# FPGA.net
KiCad netlist of a schematic drawn in Altium Designer
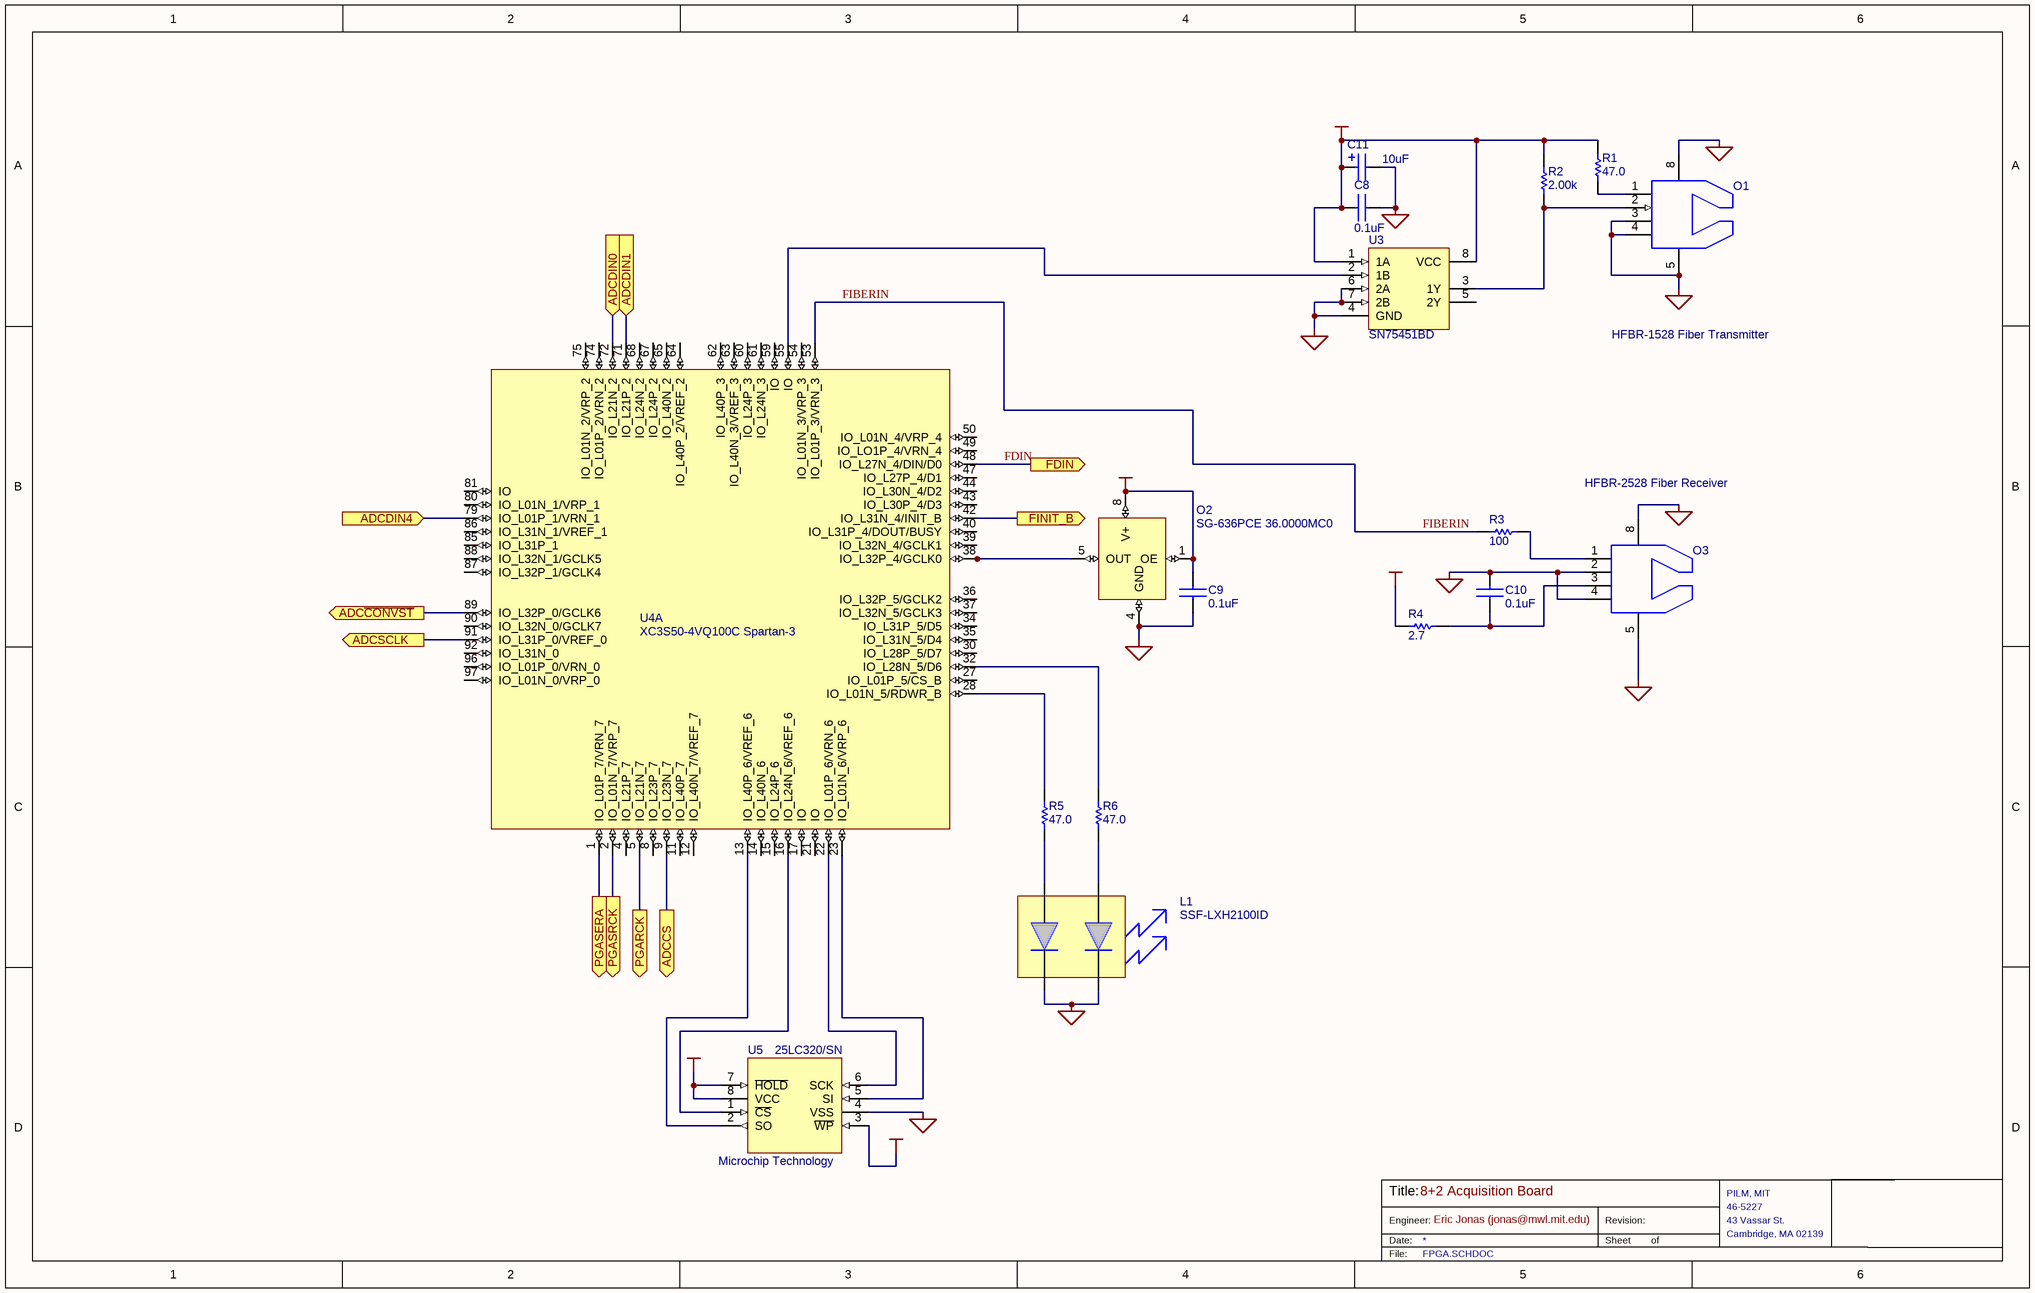
[diagram p0: FPGA.SCHDOC]

(export (version "E")
  (design (tool "Eeschema 10.0.6"))
  (components
    (comp (ref "C8")
      (value "0.1uF")
      (footprint "0603")
      (description "Standard Capacitor")
      (fields (field (name "Comment") "CAPACITOR"))
      (libsource (lib "parts") (part "CAPACITOR"))
    )
    (comp (ref "C9")
      (value "0.1uF")
      (footprint "0603")
      (description "Standard Capacitor")
      (fields (field (name "Comment") "CAPACITOR"))
      (libsource (lib "parts") (part "CAPACITOR"))
    )
    (comp (ref "C10")
      (value "0.1uF")
      (footprint "0603")
      (description "Standard Capacitor")
      (fields (field (name "Comment") "CAPACITOR"))
      (libsource (lib "parts") (part "CAPACITOR"))
    )
    (comp (ref "C11")
      (value "10uF")
      (footprint "3216")
      (description "Standard Capacitor")
      (fields (field (name "Comment") "Tantalum"))
      (libsource (lib "parts") (part "POLCAP"))
    )
    (comp (ref "L1")
      (value "SSF-LXH2100ID")
      (footprint "LUMEX DUAL RT-ANG LED")
      (description "Dual LED")
      (libsource (lib "parts") (part "DUAL LED"))
    )
    (comp (ref "O1")
      (value "HFBR-1528 Fiber Transmitter")
      (footprint "HPVL")
      (description "Low-cost fiber transmitter")
      (libsource (lib "parts") (part "HFBR-1528"))
    )
    (comp (ref "O2")
      (value "SG-636PCE 36.0000MC0")
      (footprint "SG636PCE")
      (description "Epson CMOS/TTL Oscillator")
      (libsource (lib "parts") (part "SG-636PCE"))
    )
    (comp (ref "O3")
      (value "HFBR-2528 Fiber Receiver")
      (footprint "HPVL")
      (description "Low-cost fiber receiver")
      (libsource (lib "parts") (part "HFBR-2528"))
    )
    (comp (ref "R1")
      (value "47.0")
      (footprint "0603")
      (description "Standard Passive Resistor")
      (fields (field (name "Comment") "RESISTOR"))
      (libsource (lib "parts") (part "RESISTOR"))
    )
    (comp (ref "R2")
      (value "2.00k")
      (footprint "0603")
      (description "Standard Passive Resistor")
      (fields (field (name "Comment") "RESISTOR"))
      (libsource (lib "parts") (part "RESISTOR"))
    )
    (comp (ref "R3")
      (value "100")
      (footprint "0603")
      (description "Standard Passive Resistor")
      (fields (field (name "Comment") "RESISTOR"))
      (libsource (lib "parts") (part "RESISTOR"))
    )
    (comp (ref "R4")
      (value "2.7")
      (footprint "0603")
      (description "Standard Passive Resistor")
      (fields (field (name "Comment") "RESISTOR"))
      (libsource (lib "parts") (part "RESISTOR"))
    )
    (comp (ref "R5")
      (value "47.0")
      (footprint "0603")
      (description "Standard Passive Resistor")
      (fields (field (name "Comment") "RESISTOR"))
      (libsource (lib "parts") (part "RESISTOR"))
    )
    (comp (ref "R6")
      (value "47.0")
      (footprint "0603")
      (description "Standard Passive Resistor")
      (fields (field (name "Comment") "RESISTOR"))
      (libsource (lib "parts") (part "RESISTOR"))
    )
    (comp (ref "U3")
      (value "SN75451BD")
      (footprint "SO-G8/E2.5")
      (description "Dual Peripheral Driver")
      (fields (field (name "MANUFACTURER") "Texas Instruments") (field (name "PUBLISHER") "Altium Limited"))
      (libsource (lib "TI Interface Peripheral Driver") (part "SN75451BD"))
    )
    (comp (ref "U4")
      (value "XC3S50-4VQ100C Spartan-3")
      (footprint "F-QFP14X14-G100/N")
      (description "Xilinx Spartan-3 VQ100")
      (libsource (lib "parts") (part "XC3S50-4VQ100C"))
    )
    (comp (ref "U5")
      (value "25LC320/SN")
      (footprint "SO-G8/E2.9")
      (description "32k SPI Bus Serial EEPROM")
      (fields (field (name "VENDOR") "Microchip Technology"))
      (libsource (lib "parts") (part "25LC320-SOIC"))
    )
  )
  (nets
    (net (code "1") (name "+5VCC") (class "Default")
      (node (ref "C11") (pin "1") (pintype "passive"))
      (node (ref "C8") (pin "1") (pintype "passive"))
      (node (ref "R1") (pin "2") (pintype "passive"))
      (node (ref "R2") (pin "2") (pintype "passive"))
      (node (ref "R4") (pin "1") (pintype "passive"))
      (node (ref "U3") (pin "1") (pinfunction "1A_1") (pintype "input"))
      (node (ref "U3") (pin "8") (pinfunction "VCC_8") (pintype "power_in"))
    )
    (net (code "2") (name "/ADCCS") (class "Default")
      (node (ref "U4") (pin "9") (pinfunction "IO_L23N_7_9") (pintype "bidirectional"))
    )
    (net (code "3") (name "/ADCDIN0") (class "Default")
      (node (ref "U4") (pin "72") (pinfunction "IO_L21N_2_72") (pintype "bidirectional"))
    )
    (net (code "4") (name "/ADCDIN1") (class "Default")
      (node (ref "U4") (pin "71") (pinfunction "IO_L21P_2_71") (pintype "bidirectional"))
    )
    (net (code "5") (name "/ADCDIN4") (class "Default")
      (node (ref "U4") (pin "79") (pinfunction "IO_L01P_1/VRN_1_79") (pintype "bidirectional"))
    )
    (net (code "6") (name "/ADCSCLK") (class "Default")
      (node (ref "U4") (pin "91") (pinfunction "IO_L31P_0/VREF_0_91") (pintype "bidirectional"))
    )
    (net (code "7") (name "/ADC~{CONVST}") (class "Default")
      (node (ref "U4") (pin "89") (pinfunction "IO_L32P_0/GCLK6_89") (pintype "bidirectional"))
    )
    (net (code "8") (name "/FDIN") (class "Default")
      (node (ref "U4") (pin "48") (pinfunction "IO_L27N_4/DIN/D0_48") (pintype "bidirectional"))
    )
    (net (code "9") (name "/FIBERIN") (class "Default")
      (node (ref "R3") (pin "1") (pintype "passive"))
      (node (ref "U4") (pin "53") (pinfunction "IO_L01P_3/VRN_3_53") (pintype "bidirectional"))
    )
    (net (code "10") (name "/FINIT_B") (class "Default")
      (node (ref "U4") (pin "42") (pinfunction "IO_L31N_4/INIT_B_42") (pintype "bidirectional"))
    )
    (net (code "11") (name "/PGARCK") (class "Default")
      (node (ref "U4") (pin "5") (pinfunction "IO_L21N_7_5") (pintype "bidirectional"))
    )
    (net (code "12") (name "/PGASERA") (class "Default")
      (node (ref "U4") (pin "1") (pinfunction "IO_L01P_7/VRN_7_1") (pintype "bidirectional"))
    )
    (net (code "13") (name "/PGASRCK") (class "Default")
      (node (ref "U4") (pin "2") (pinfunction "IO_L01N_7/VRP_7_2") (pintype "bidirectional"))
    )
    (net (code "14") (name "GND") (class "Default")
      (node (ref "C10") (pin "2") (pintype "passive"))
      (node (ref "C11") (pin "2") (pintype "passive"))
      (node (ref "C8") (pin "2") (pintype "passive"))
      (node (ref "C9") (pin "2") (pintype "passive"))
      (node (ref "L1") (pin "2") (pinfunction "2_2") (pintype "passive"))
      (node (ref "L1") (pin "4") (pinfunction "C2_4") (pintype "passive"))
      (node (ref "O1") (pin "3") (pintype "power_in"))
      (node (ref "O1") (pin "4") (pintype "power_in"))
      (node (ref "O1") (pin "5") (pintype "power_in"))
      (node (ref "O1") (pin "8") (pintype "power_in"))
      (node (ref "O2") (pin "4") (pinfunction "GND_4") (pintype "bidirectional"))
      (node (ref "O3") (pin "2") (pintype "power_in"))
      (node (ref "O3") (pin "4") (pintype "power_in"))
      (node (ref "O3") (pin "5") (pintype "power_in"))
      (node (ref "O3") (pin "8") (pintype "power_in"))
      (node (ref "U3") (pin "4") (pinfunction "GND_4") (pintype "power_in"))
      (node (ref "U3") (pin "6") (pinfunction "2A_6") (pintype "input"))
      (node (ref "U3") (pin "7") (pinfunction "2B_7") (pintype "input"))
      (node (ref "U5") (pin "4") (pinfunction "VSS_4") (pintype "power_in"))
    )
    (net (code "15") (name "Net-(C10-Pad1)") (class "Default")
      (node (ref "C10") (pin "1") (pintype "passive"))
      (node (ref "O3") (pin "3") (pintype "power_in"))
      (node (ref "R4") (pin "2") (pintype "passive"))
    )
    (net (code "16") (name "Net-(L1-A1)") (class "Default")
      (node (ref "L1") (pin "1") (pinfunction "A1_1") (pintype "passive"))
      (node (ref "R5") (pin "2") (pintype "passive"))
    )
    (net (code "17") (name "Net-(L1-A2)") (class "Default")
      (node (ref "L1") (pin "3") (pinfunction "A2_3") (pintype "passive"))
      (node (ref "R6") (pin "2") (pintype "passive"))
    )
    (net (code "18") (name "Net-(O1-Pad1)") (class "Default")
      (node (ref "O1") (pin "1") (pintype "power_in"))
      (node (ref "R1") (pin "1") (pintype "passive"))
    )
    (net (code "19") (name "Net-(O2-OUT)") (class "Default")
      (node (ref "O2") (pin "5") (pinfunction "OUT_5") (pintype "bidirectional"))
      (node (ref "U4") (pin "38") (pinfunction "IO_L32P_4/GCLK0_38") (pintype "bidirectional"))
    )
    (net (code "20") (name "Net-(O3-Pad1)") (class "Default")
      (node (ref "O3") (pin "1") (pintype "power_in"))
      (node (ref "R3") (pin "2") (pintype "passive"))
    )
    (net (code "21") (name "Net-(U3-1B)") (class "Default")
      (node (ref "U3") (pin "2") (pinfunction "1B_2") (pintype "input"))
      (node (ref "U4") (pin "55") (pinfunction "IO_55") (pintype "bidirectional"))
    )
    (net (code "22") (name "Net-(U3-1Y)") (class "Default")
      (node (ref "O1") (pin "2") (pintype "input"))
      (node (ref "R2") (pin "1") (pintype "passive"))
      (node (ref "U3") (pin "3") (pinfunction "1Y_3") (pintype "open_collector"))
    )
    (net (code "23") (name "Net-(U4A-IO_L01N_5{slash}RDWR_B)") (class "Default")
      (node (ref "R5") (pin "1") (pintype "passive"))
      (node (ref "U4") (pin "28") (pinfunction "IO_L01N_5/RDWR_B_28") (pintype "bidirectional"))
    )
    (net (code "24") (name "Net-(U4A-IO_L01N_6{slash}VRP_6)") (class "Default")
      (node (ref "U4") (pin "23") (pinfunction "IO_L01N_6/VRP_6_23") (pintype "bidirectional"))
      (node (ref "U5") (pin "5") (pinfunction "SI_5") (pintype "input"))
    )
    (net (code "25") (name "Net-(U4A-IO_L01P_6{slash}VRN_6)") (class "Default")
      (node (ref "U4") (pin "22") (pinfunction "IO_L01P_6/VRN_6_22") (pintype "bidirectional"))
      (node (ref "U5") (pin "6") (pinfunction "SCK_6") (pintype "input"))
    )
    (net (code "26") (name "Net-(U4A-IO_L24N_6{slash}VREF_6)") (class "Default")
      (node (ref "U4") (pin "16") (pinfunction "IO_L24N_6/VREF_6_16") (pintype "bidirectional"))
      (node (ref "U5") (pin "1") (pinfunction "~{CS}_1") (pintype "input"))
    )
    (net (code "27") (name "Net-(U4A-IO_L28N_5{slash}D6)") (class "Default")
      (node (ref "R6") (pin "1") (pintype "passive"))
      (node (ref "U4") (pin "32") (pinfunction "IO_L28N_5/D6_32") (pintype "bidirectional"))
    )
    (net (code "28") (name "Net-(U4A-IO_L40P_6{slash}VREF_6)") (class "Default")
      (node (ref "U4") (pin "13") (pinfunction "IO_L40P_6/VREF_6_13") (pintype "bidirectional"))
      (node (ref "U5") (pin "2") (pinfunction "SO_2") (pintype "output"))
    )
    (net (code "29") (name "VCC") (class "Default")
      (node (ref "C9") (pin "1") (pintype "passive"))
      (node (ref "O2") (pin "1") (pinfunction "OE_1") (pintype "bidirectional"))
      (node (ref "O2") (pin "8") (pinfunction "V+_8") (pintype "bidirectional"))
      (node (ref "U5") (pin "3") (pinfunction "~{WP}_3") (pintype "input"))
      (node (ref "U5") (pin "7") (pinfunction "~{HOLD}_7") (pintype "input"))
      (node (ref "U5") (pin "8") (pinfunction "VCC_8") (pintype "power_in"))
    )
    (net (code "30") (name "unconnected-(U3-2Y-Pad5)") (class "Default")
      (node (ref "U3") (pin "5") (pinfunction "2Y_5") (pintype "open_collector"))
    )
    (net (code "31") (name "unconnected-(U4A-IO-Pad17)") (class "Default")
      (node (ref "U4") (pin "17") (pinfunction "IO_17") (pintype "bidirectional"))
    )
    (net (code "32") (name "unconnected-(U4A-IO-Pad21)") (class "Default")
      (node (ref "U4") (pin "21") (pinfunction "IO_21") (pintype "bidirectional"))
    )
    (net (code "33") (name "unconnected-(U4A-IO-Pad59)") (class "Default")
      (node (ref "U4") (pin "59") (pinfunction "IO_59") (pintype "bidirectional"))
    )
    (net (code "34") (name "unconnected-(U4A-IO-Pad81)") (class "Default")
      (node (ref "U4") (pin "81") (pinfunction "IO_81") (pintype "bidirectional"))
    )
    (net (code "35") (name "unconnected-(U4A-IO_L01N_0{slash}VRP_0-Pad97)") (class "Default")
      (node (ref "U4") (pin "97") (pinfunction "IO_L01N_0/VRP_0_97") (pintype "bidirectional"))
    )
    (net (code "36") (name "unconnected-(U4A-IO_L01N_1{slash}VRP_1-Pad80)") (class "Default")
      (node (ref "U4") (pin "80") (pinfunction "IO_L01N_1/VRP_1_80") (pintype "bidirectional"))
    )
    (net (code "37") (name "unconnected-(U4A-IO_L01N_2{slash}VRP_2-Pad75)") (class "Default")
      (node (ref "U4") (pin "75") (pinfunction "IO_L01N_2/VRP_2_75") (pintype "bidirectional"))
    )
    (net (code "38") (name "unconnected-(U4A-IO_L01N_3{slash}VRP_3-Pad54)") (class "Default")
      (node (ref "U4") (pin "54") (pinfunction "IO_L01N_3/VRP_3_54") (pintype "bidirectional"))
    )
    (net (code "39") (name "unconnected-(U4A-IO_L01N_4{slash}VRP_4-Pad50)") (class "Default")
      (node (ref "U4") (pin "50") (pinfunction "IO_L01N_4/VRP_4_50") (pintype "bidirectional"))
    )
    (net (code "40") (name "unconnected-(U4A-IO_L01P_0{slash}VRN_0-Pad96)") (class "Default")
      (node (ref "U4") (pin "96") (pinfunction "IO_L01P_0/VRN_0_96") (pintype "bidirectional"))
    )
    (net (code "41") (name "unconnected-(U4A-IO_L01P_2{slash}VRN_2-Pad74)") (class "Default")
      (node (ref "U4") (pin "74") (pinfunction "IO_L01P_2/VRN_2_74") (pintype "bidirectional"))
    )
    (net (code "42") (name "unconnected-(U4A-IO_L01P_5{slash}CS_B-Pad27)") (class "Default")
      (node (ref "U4") (pin "27") (pinfunction "IO_L01P_5/CS_B_27") (pintype "bidirectional"))
    )
    (net (code "43") (name "unconnected-(U4A-IO_L21P_7-Pad4)") (class "Default")
      (node (ref "U4") (pin "4") (pinfunction "IO_L21P_7_4") (pintype "bidirectional"))
    )
    (net (code "44") (name "unconnected-(U4A-IO_L23P_7-Pad8)") (class "Default")
      (node (ref "U4") (pin "8") (pinfunction "IO_L23P_7_8") (pintype "bidirectional"))
    )
    (net (code "45") (name "unconnected-(U4A-IO_L24N_2-Pad68)") (class "Default")
      (node (ref "U4") (pin "68") (pinfunction "IO_L24N_2_68") (pintype "bidirectional"))
    )
    (net (code "46") (name "unconnected-(U4A-IO_L24N_3-Pad61)") (class "Default")
      (node (ref "U4") (pin "61") (pinfunction "IO_L24N_3_61") (pintype "bidirectional"))
    )
    (net (code "47") (name "unconnected-(U4A-IO_L24P_2-Pad67)") (class "Default")
      (node (ref "U4") (pin "67") (pinfunction "IO_L24P_2_67") (pintype "bidirectional"))
    )
    (net (code "48") (name "unconnected-(U4A-IO_L24P_3-Pad60)") (class "Default")
      (node (ref "U4") (pin "60") (pinfunction "IO_L24P_3_60") (pintype "bidirectional"))
    )
    (net (code "49") (name "unconnected-(U4A-IO_L24P_6-Pad15)") (class "Default")
      (node (ref "U4") (pin "15") (pinfunction "IO_L24P_6_15") (pintype "bidirectional"))
    )
    (net (code "50") (name "unconnected-(U4A-IO_L27P_4{slash}D1-Pad47)") (class "Default")
      (node (ref "U4") (pin "47") (pinfunction "IO_L27P_4/D1_47") (pintype "bidirectional"))
    )
    (net (code "51") (name "unconnected-(U4A-IO_L28P_5{slash}D7-Pad30)") (class "Default")
      (node (ref "U4") (pin "30") (pinfunction "IO_L28P_5/D7_30") (pintype "bidirectional"))
    )
    (net (code "52") (name "unconnected-(U4A-IO_L30N_4{slash}D2-Pad44)") (class "Default")
      (node (ref "U4") (pin "44") (pinfunction "IO_L30N_4/D2_44") (pintype "bidirectional"))
    )
    (net (code "53") (name "unconnected-(U4A-IO_L30P_4{slash}D3-Pad43)") (class "Default")
      (node (ref "U4") (pin "43") (pinfunction "IO_L30P_4/D3_43") (pintype "bidirectional"))
    )
    (net (code "54") (name "unconnected-(U4A-IO_L31N_0-Pad92)") (class "Default")
      (node (ref "U4") (pin "92") (pinfunction "IO_L31N_0_92") (pintype "bidirectional"))
    )
    (net (code "55") (name "unconnected-(U4A-IO_L31N_1{slash}VREF_1-Pad86)") (class "Default")
      (node (ref "U4") (pin "86") (pinfunction "IO_L31N_1/VREF_1_86") (pintype "bidirectional"))
    )
    (net (code "56") (name "unconnected-(U4A-IO_L31N_5{slash}D4-Pad35)") (class "Default")
      (node (ref "U4") (pin "35") (pinfunction "IO_L31N_5/D4_35") (pintype "bidirectional"))
    )
    (net (code "57") (name "unconnected-(U4A-IO_L31P_1-Pad85)") (class "Default")
      (node (ref "U4") (pin "85") (pinfunction "IO_L31P_1_85") (pintype "bidirectional"))
    )
    (net (code "58") (name "unconnected-(U4A-IO_L31P_4{slash}DOUT{slash}BUSY-Pad40)") (class "Default")
      (node (ref "U4") (pin "40") (pinfunction "IO_L31P_4/DOUT/BUSY_40") (pintype "bidirectional"))
    )
    (net (code "59") (name "unconnected-(U4A-IO_L31P_5{slash}D5-Pad34)") (class "Default")
      (node (ref "U4") (pin "34") (pinfunction "IO_L31P_5/D5_34") (pintype "bidirectional"))
    )
    (net (code "60") (name "unconnected-(U4A-IO_L32N_0{slash}GCLK7-Pad90)") (class "Default")
      (node (ref "U4") (pin "90") (pinfunction "IO_L32N_0/GCLK7_90") (pintype "bidirectional"))
    )
    (net (code "61") (name "unconnected-(U4A-IO_L32N_1{slash}GCLK5-Pad88)") (class "Default")
      (node (ref "U4") (pin "88") (pinfunction "IO_L32N_1/GCLK5_88") (pintype "bidirectional"))
    )
    (net (code "62") (name "unconnected-(U4A-IO_L32N_4{slash}GCLK1-Pad39)") (class "Default")
      (node (ref "U4") (pin "39") (pinfunction "IO_L32N_4/GCLK1_39") (pintype "bidirectional"))
    )
    (net (code "63") (name "unconnected-(U4A-IO_L32N_5{slash}GCLK3-Pad37)") (class "Default")
      (node (ref "U4") (pin "37") (pinfunction "IO_L32N_5/GCLK3_37") (pintype "bidirectional"))
    )
    (net (code "64") (name "unconnected-(U4A-IO_L32P_1{slash}GCLK4-Pad87)") (class "Default")
      (node (ref "U4") (pin "87") (pinfunction "IO_L32P_1/GCLK4_87") (pintype "bidirectional"))
    )
    (net (code "65") (name "unconnected-(U4A-IO_L32P_5{slash}GCLK2-Pad36)") (class "Default")
      (node (ref "U4") (pin "36") (pinfunction "IO_L32P_5/GCLK2_36") (pintype "bidirectional"))
    )
    (net (code "66") (name "unconnected-(U4A-IO_L40N_2-Pad65)") (class "Default")
      (node (ref "U4") (pin "65") (pinfunction "IO_L40N_2_65") (pintype "bidirectional"))
    )
    (net (code "67") (name "unconnected-(U4A-IO_L40N_3{slash}VREF_3-Pad63)") (class "Default")
      (node (ref "U4") (pin "63") (pinfunction "IO_L40N_3/VREF_3_63") (pintype "bidirectional"))
    )
    (net (code "68") (name "unconnected-(U4A-IO_L40N_6-Pad14)") (class "Default")
      (node (ref "U4") (pin "14") (pinfunction "IO_L40N_6_14") (pintype "bidirectional"))
    )
    (net (code "69") (name "unconnected-(U4A-IO_L40N_7{slash}VREF_7-Pad12)") (class "Default")
      (node (ref "U4") (pin "12") (pinfunction "IO_L40N_7/VREF_7_12") (pintype "bidirectional"))
    )
    (net (code "70") (name "unconnected-(U4A-IO_L40P_2{slash}VREF_2-Pad64)") (class "Default")
      (node (ref "U4") (pin "64") (pinfunction "IO_L40P_2/VREF_2_64") (pintype "bidirectional"))
    )
    (net (code "71") (name "unconnected-(U4A-IO_L40P_3-Pad62)") (class "Default")
      (node (ref "U4") (pin "62") (pinfunction "IO_L40P_3_62") (pintype "bidirectional"))
    )
    (net (code "72") (name "unconnected-(U4A-IO_L40P_7-Pad11)") (class "Default")
      (node (ref "U4") (pin "11") (pinfunction "IO_L40P_7_11") (pintype "bidirectional"))
    )
    (net (code "73") (name "unconnected-(U4A-IO_LO1P_4{slash}VRN_4-Pad49)") (class "Default")
      (node (ref "U4") (pin "49") (pinfunction "IO_LO1P_4/VRN_4_49") (pintype "bidirectional"))
    )
  )
)
